# arduino_due_component_connection.net
KiCad netlist of a schematic drawn in Altium Designer
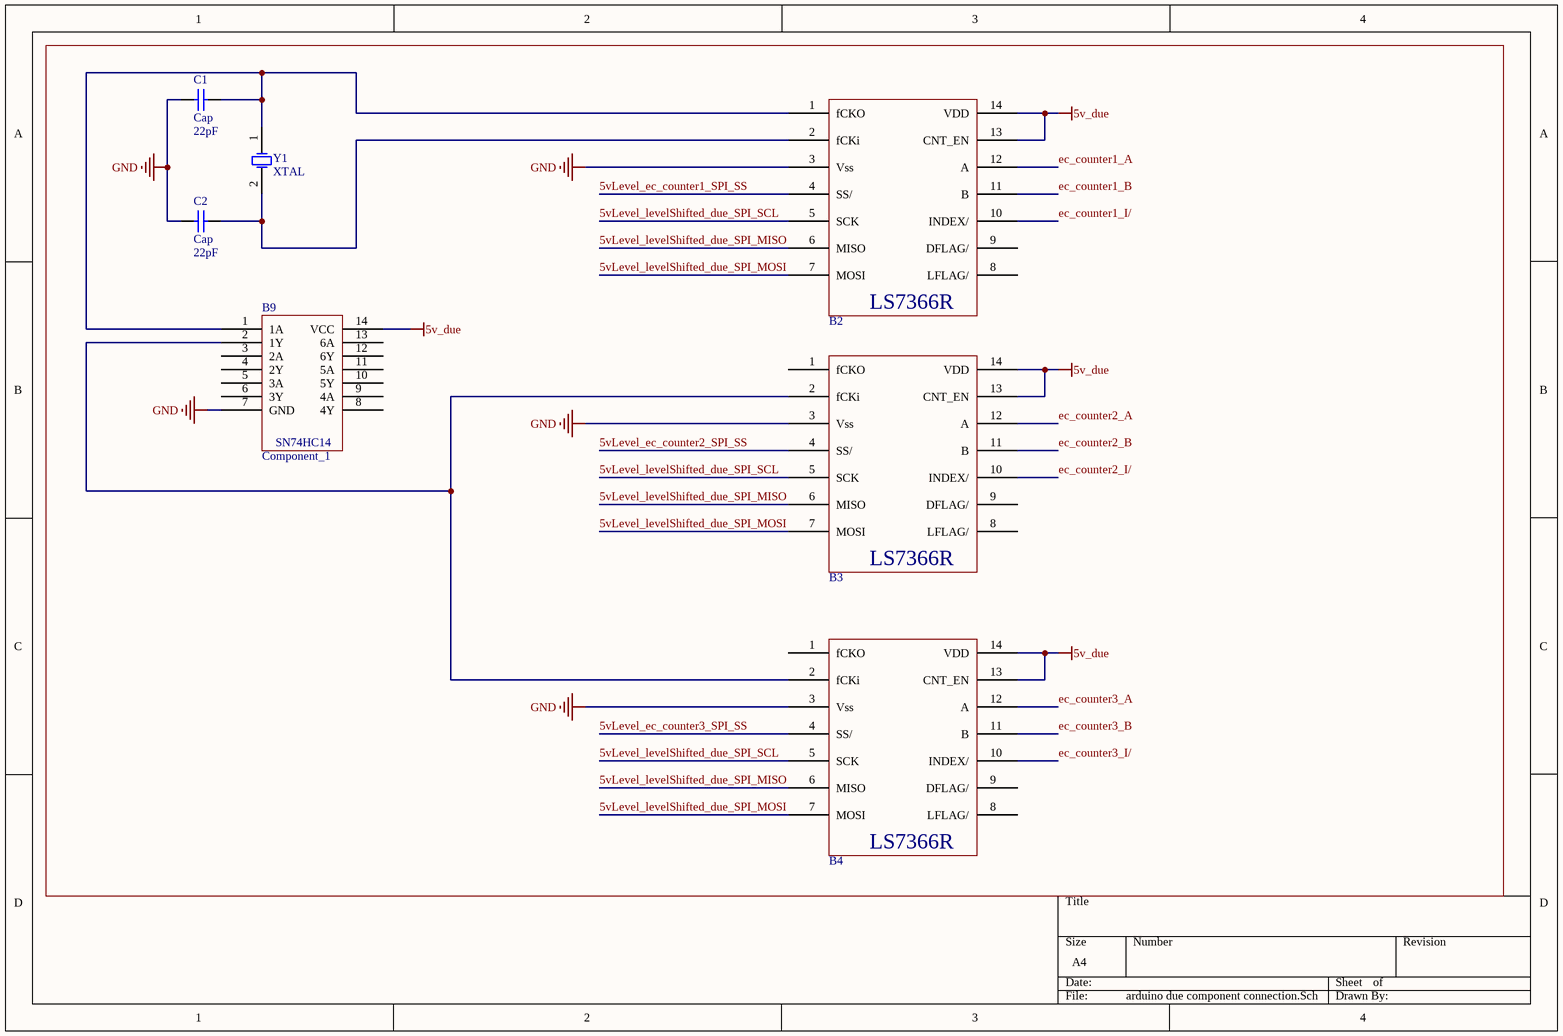
[diagram p0: arduino due component connection.SchDoc]

(export (version "E")
  (design (tool "Eeschema 10.0.6"))
  (components
    (comp (ref "B2")
      (value "Component_1")
      (footprint "DIP-14")
      (libsource (lib "LS7366R") (part "Component_1"))
    )
    (comp (ref "B3")
      (value "Component_1")
      (footprint "DIP-14")
      (libsource (lib "LS7366R") (part "Component_1"))
    )
    (comp (ref "B4")
      (value "Component_1")
      (footprint "DIP-14")
      (libsource (lib "LS7366R") (part "Component_1"))
    )
    (comp (ref "B9")
      (value "Component_1")
      (footprint "DIP-14")
      (libsource (lib "SN74HC14") (part "Component_1"))
    )
    (comp (ref "C1")
      (value "Cap")
      (footprint "RAD-0.1")
      (description "Capacitor")
      (fields (field (name "ALTIUM_VALUE") "22pF") (field (name "PUBLISHER") "Altium Limited"))
      (libsource (lib "Miscellaneous Devices") (part "Cap"))
    )
    (comp (ref "C2")
      (value "Cap")
      (footprint "RAD-0.1")
      (description "Capacitor")
      (fields (field (name "ALTIUM_VALUE") "22pF") (field (name "PUBLISHER") "Altium Limited"))
      (libsource (lib "Miscellaneous Devices") (part "Cap"))
    )
    (comp (ref "Y1")
      (value "XTAL")
      (footprint "R38")
      (description "Crystal Oscillator")
      (fields (field (name "PUBLISHER") "Altium Limited"))
      (libsource (lib "Miscellaneous Devices") (part "XTAL"))
    )
  )
  (nets
    (net (code "1") (name "/5vLevel_ec_counter1_SPI_SS") (class "Default")
      (node (ref "B2") (pin "4") (pinfunction "SS/_4") (pintype "passive"))
    )
    (net (code "2") (name "/5vLevel_ec_counter2_SPI_SS") (class "Default")
      (node (ref "B3") (pin "4") (pinfunction "SS/_4") (pintype "passive"))
    )
    (net (code "3") (name "/5vLevel_ec_counter3_SPI_SS") (class "Default")
      (node (ref "B4") (pin "4") (pinfunction "SS/_4") (pintype "passive"))
    )
    (net (code "4") (name "/5vLevel_levelShifted_due_SPI_MISO") (class "Default")
      (node (ref "B2") (pin "6") (pinfunction "MISO_6") (pintype "passive"))
      (node (ref "B3") (pin "6") (pinfunction "MISO_6") (pintype "passive"))
      (node (ref "B4") (pin "6") (pinfunction "MISO_6") (pintype "passive"))
    )
    (net (code "5") (name "/5vLevel_levelShifted_due_SPI_MOSI") (class "Default")
      (node (ref "B2") (pin "7") (pinfunction "MOSI_7") (pintype "passive"))
      (node (ref "B3") (pin "7") (pinfunction "MOSI_7") (pintype "passive"))
      (node (ref "B4") (pin "7") (pinfunction "MOSI_7") (pintype "passive"))
    )
    (net (code "6") (name "/5vLevel_levelShifted_due_SPI_SCL") (class "Default")
      (node (ref "B2") (pin "5") (pinfunction "SCK_5") (pintype "passive"))
      (node (ref "B3") (pin "5") (pinfunction "SCK_5") (pintype "passive"))
      (node (ref "B4") (pin "5") (pinfunction "SCK_5") (pintype "passive"))
    )
    (net (code "7") (name "/ec_counter1_A") (class "Default")
      (node (ref "B2") (pin "12") (pinfunction "A_12") (pintype "passive"))
    )
    (net (code "8") (name "/ec_counter1_B") (class "Default")
      (node (ref "B2") (pin "11") (pinfunction "B_11") (pintype "passive"))
    )
    (net (code "9") (name "/ec_counter1_I{slash}") (class "Default")
      (node (ref "B2") (pin "10") (pinfunction "INDEX/_10") (pintype "passive"))
    )
    (net (code "10") (name "/ec_counter2_A") (class "Default")
      (node (ref "B3") (pin "12") (pinfunction "A_12") (pintype "passive"))
    )
    (net (code "11") (name "/ec_counter2_B") (class "Default")
      (node (ref "B3") (pin "11") (pinfunction "B_11") (pintype "passive"))
    )
    (net (code "12") (name "/ec_counter2_I{slash}") (class "Default")
      (node (ref "B3") (pin "10") (pinfunction "INDEX/_10") (pintype "passive"))
    )
    (net (code "13") (name "/ec_counter3_A") (class "Default")
      (node (ref "B4") (pin "12") (pinfunction "A_12") (pintype "passive"))
    )
    (net (code "14") (name "/ec_counter3_B") (class "Default")
      (node (ref "B4") (pin "11") (pinfunction "B_11") (pintype "passive"))
    )
    (net (code "15") (name "/ec_counter3_I{slash}") (class "Default")
      (node (ref "B4") (pin "10") (pinfunction "INDEX/_10") (pintype "passive"))
    )
    (net (code "16") (name "5v_due") (class "Default")
      (node (ref "B2") (pin "13") (pinfunction "CNT_EN_13") (pintype "passive"))
      (node (ref "B2") (pin "14") (pinfunction "VDD_14") (pintype "passive"))
      (node (ref "B3") (pin "13") (pinfunction "CNT_EN_13") (pintype "passive"))
      (node (ref "B3") (pin "14") (pinfunction "VDD_14") (pintype "passive"))
      (node (ref "B4") (pin "13") (pinfunction "CNT_EN_13") (pintype "passive"))
      (node (ref "B4") (pin "14") (pinfunction "VDD_14") (pintype "passive"))
      (node (ref "B9") (pin "14") (pinfunction "VCC_14") (pintype "passive"))
    )
    (net (code "17") (name "GND") (class "Default")
      (node (ref "B2") (pin "3") (pinfunction "Vss_3") (pintype "passive"))
      (node (ref "B3") (pin "3") (pinfunction "Vss_3") (pintype "passive"))
      (node (ref "B4") (pin "3") (pinfunction "Vss_3") (pintype "passive"))
      (node (ref "B9") (pin "7") (pinfunction "GND_7") (pintype "passive"))
      (node (ref "C1") (pin "1") (pinfunction "1_1") (pintype "passive"))
      (node (ref "C2") (pin "1") (pinfunction "1_1") (pintype "passive"))
    )
    (net (code "18") (name "Net-(B2-fCKO)") (class "Default")
      (node (ref "B2") (pin "1") (pinfunction "fCKO_1") (pintype "passive"))
      (node (ref "B9") (pin "1") (pinfunction "1A_1") (pintype "passive"))
      (node (ref "C1") (pin "2") (pinfunction "2_2") (pintype "passive"))
      (node (ref "Y1") (pin "1") (pinfunction "OSC1_1") (pintype "passive"))
    )
    (net (code "19") (name "Net-(B2-fCKi)") (class "Default")
      (node (ref "B2") (pin "2") (pinfunction "fCKi_2") (pintype "passive"))
      (node (ref "C2") (pin "2") (pinfunction "2_2") (pintype "passive"))
      (node (ref "Y1") (pin "2") (pinfunction "OSC2_2") (pintype "passive"))
    )
    (net (code "20") (name "Net-(B3-fCKi)") (class "Default")
      (node (ref "B3") (pin "2") (pinfunction "fCKi_2") (pintype "passive"))
      (node (ref "B4") (pin "2") (pinfunction "fCKi_2") (pintype "passive"))
      (node (ref "B9") (pin "2") (pinfunction "1Y_2") (pintype "passive"))
    )
    (net (code "21") (name "unconnected-(B2-DFLAG{slash}-Pad9)") (class "Default")
      (node (ref "B2") (pin "9") (pinfunction "DFLAG/_9") (pintype "passive"))
    )
    (net (code "22") (name "unconnected-(B2-LFLAG{slash}-Pad8)") (class "Default")
      (node (ref "B2") (pin "8") (pinfunction "LFLAG/_8") (pintype "passive"))
    )
    (net (code "23") (name "unconnected-(B3-DFLAG{slash}-Pad9)") (class "Default")
      (node (ref "B3") (pin "9") (pinfunction "DFLAG/_9") (pintype "passive"))
    )
    (net (code "24") (name "unconnected-(B3-LFLAG{slash}-Pad8)") (class "Default")
      (node (ref "B3") (pin "8") (pinfunction "LFLAG/_8") (pintype "passive"))
    )
    (net (code "25") (name "unconnected-(B3-fCKO-Pad1)") (class "Default")
      (node (ref "B3") (pin "1") (pinfunction "fCKO_1") (pintype "passive"))
    )
    (net (code "26") (name "unconnected-(B4-DFLAG{slash}-Pad9)") (class "Default")
      (node (ref "B4") (pin "9") (pinfunction "DFLAG/_9") (pintype "passive"))
    )
    (net (code "27") (name "unconnected-(B4-LFLAG{slash}-Pad8)") (class "Default")
      (node (ref "B4") (pin "8") (pinfunction "LFLAG/_8") (pintype "passive"))
    )
    (net (code "28") (name "unconnected-(B4-fCKO-Pad1)") (class "Default")
      (node (ref "B4") (pin "1") (pinfunction "fCKO_1") (pintype "passive"))
    )
    (net (code "29") (name "unconnected-(B9-2A-Pad3)") (class "Default")
      (node (ref "B9") (pin "3") (pinfunction "2A_3") (pintype "passive"))
    )
    (net (code "30") (name "unconnected-(B9-2Y-Pad4)") (class "Default")
      (node (ref "B9") (pin "4") (pinfunction "2Y_4") (pintype "passive"))
    )
    (net (code "31") (name "unconnected-(B9-3A-Pad5)") (class "Default")
      (node (ref "B9") (pin "5") (pinfunction "3A_5") (pintype "passive"))
    )
    (net (code "32") (name "unconnected-(B9-3Y-Pad6)") (class "Default")
      (node (ref "B9") (pin "6") (pinfunction "3Y_6") (pintype "passive"))
    )
    (net (code "33") (name "unconnected-(B9-4A-Pad9)") (class "Default")
      (node (ref "B9") (pin "9") (pinfunction "4A_9") (pintype "passive"))
    )
    (net (code "34") (name "unconnected-(B9-4Y-Pad8)") (class "Default")
      (node (ref "B9") (pin "8") (pinfunction "4Y_8") (pintype "passive"))
    )
    (net (code "35") (name "unconnected-(B9-5A-Pad11)") (class "Default")
      (node (ref "B9") (pin "11") (pinfunction "5A_11") (pintype "passive"))
    )
    (net (code "36") (name "unconnected-(B9-5Y-Pad10)") (class "Default")
      (node (ref "B9") (pin "10") (pinfunction "5Y_10") (pintype "passive"))
    )
    (net (code "37") (name "unconnected-(B9-6A-Pad13)") (class "Default")
      (node (ref "B9") (pin "13") (pinfunction "6A_13") (pintype "passive"))
    )
    (net (code "38") (name "unconnected-(B9-6Y-Pad12)") (class "Default")
      (node (ref "B9") (pin "12") (pinfunction "6Y_12") (pintype "passive"))
    )
  )
)
